# 6V_Boost_-_High_Current.net
KiCad netlist of a schematic drawn in Altium Designer
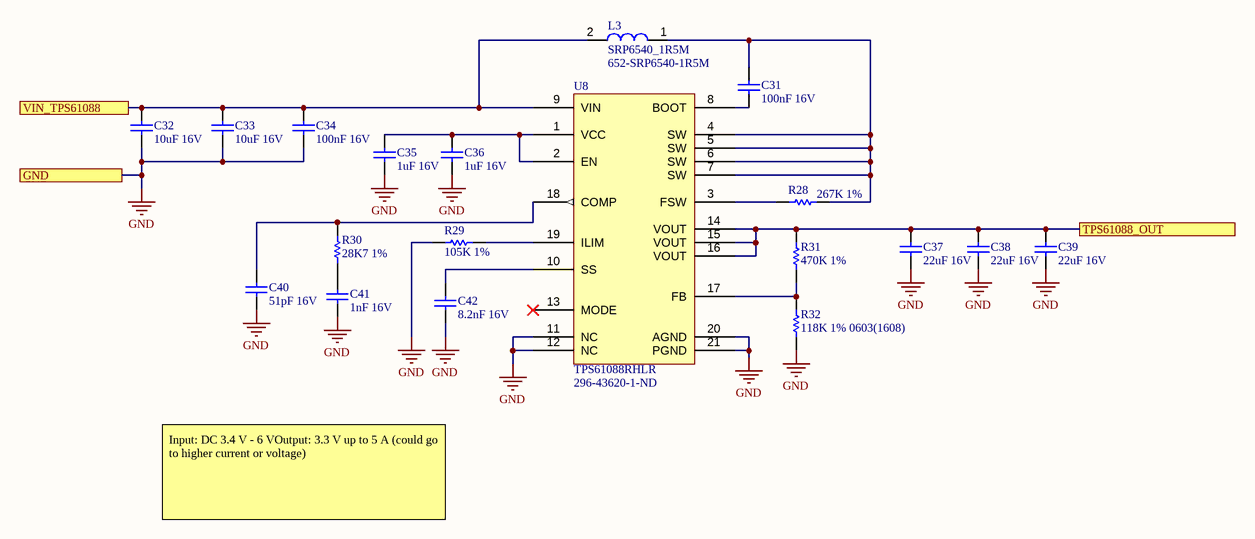
[diagram p0: 6V Boost - High Current.SchDoc]

(export (version "E")
  (design (tool "Eeschema 10.0.6"))
  (components
    (comp (ref "C31")
      (value "100nF 16V")
      (footprint "CAPC0603(1608)100_N")
      (description "CAP 100nF 16V ±10% 0603 (1608 Metric) Thickness 1mm SMD")
      (fields (field (name "TOLERANCE") "Â±10%"))
      (libsource (lib "Altium Content Vault") (part "CAP"))
    )
    (comp (ref "C32")
      (value "10uF 16V")
      (footprint "CAPC0805(2012)145_N")
      (description "CAP 10uF 16V ±10% 0805 (2012 Metric) Thickness 1.45mm SMD")
      (fields (field (name "TOLERANCE") "Â±10%"))
      (libsource (lib "Altium Content Vault") (part "CAP"))
    )
    (comp (ref "C33")
      (value "10uF 16V")
      (footprint "CAPC0805(2012)145_N")
      (description "CAP 10uF 16V ±10% 0805 (2012 Metric) Thickness 1.45mm SMD")
      (fields (field (name "TOLERANCE") "Â±10%"))
      (libsource (lib "Altium Content Vault") (part "CAP"))
    )
    (comp (ref "C34")
      (value "100nF 16V")
      (footprint "CAPC0603(1608)100_N")
      (description "CAP 100nF 16V ±10% 0603 (1608 Metric) Thickness 1mm SMD")
      (fields (field (name "TOLERANCE") "Â±10%"))
      (libsource (lib "Altium Content Vault") (part "CAP"))
    )
    (comp (ref "C35")
      (value "1uF 16V")
      (footprint "CAPC0603(1608)100_N")
      (description "CAP 1uF 16V ±5% 0603 (1608 Metric) Thickness 1mm SMD")
      (fields (field (name "TOLERANCE") "Â±5%"))
      (libsource (lib "Altium Content Vault") (part "CAP"))
    )
    (comp (ref "C36")
      (value "1uF 16V")
      (footprint "CAPC0603(1608)100_N")
      (description "CAP 1uF 16V ±5% 0603 (1608 Metric) Thickness 1mm SMD")
      (fields (field (name "TOLERANCE") "Â±5%"))
      (libsource (lib "Altium Content Vault") (part "CAP"))
    )
    (comp (ref "C37")
      (value "22uF 16V")
      (footprint "CAPC2220(5750)300_N")
      (description "CAP 22uF 16V ±20% 2220 (5750 Metric) Thickness 3mm SMD")
      (fields (field (name "TOLERANCE") "Â±20%"))
      (libsource (lib "Altium Content Vault") (part "CAP"))
    )
    (comp (ref "C38")
      (value "22uF 16V")
      (footprint "CAPC2220(5750)300_N")
      (description "CAP 22uF 16V ±20% 2220 (5750 Metric) Thickness 3mm SMD")
      (fields (field (name "TOLERANCE") "Â±20%"))
      (libsource (lib "Altium Content Vault") (part "CAP"))
    )
    (comp (ref "C39")
      (value "22uF 16V")
      (footprint "CAPC2220(5750)300_N")
      (description "CAP 22uF 16V ±20% 2220 (5750 Metric) Thickness 3mm SMD")
      (fields (field (name "TOLERANCE") "Â±20%"))
      (libsource (lib "Altium Content Vault") (part "CAP"))
    )
    (comp (ref "C40")
      (value "51pF 16V")
      (footprint "CAPC0603(1608)100_L")
      (description "CAP 51pF 16V ±5% 0603 (1608 Metric) Thickness 1mm SMD")
      (fields (field (name "TOLERANCE") "Â±5%"))
      (libsource (lib "Altium Content Vault") (part "CAP"))
    )
    (comp (ref "C41")
      (value "1nF 16V")
      (footprint "CAPC0603(1608)100_L")
      (description "CAP 1nF 16V ±1% 0603 (1608 Metric) Thickness 1mm SMD")
      (fields (field (name "TOLERANCE") "Â±1%"))
      (libsource (lib "Altium Content Vault") (part "CAP"))
    )
    (comp (ref "C42")
      (value "8.2nF 16V")
      (footprint "CAPC0603(1608)100_M")
      (description "CAP 8.2nF 16V ±5% 0603 (1608 Metric) Thickness 1mm SMD")
      (fields (field (name "TOLERANCE") "Â±5%"))
      (libsource (lib "Altium Content Vault") (part "CAP"))
    )
    (comp (ref "L3")
      (value "SRP6540_1R5M")
      (footprint "SRP6540_1R5M")
      (description "1.5µH Shielded Wirewound Inductor 11A 10 mOhm Max Nonstandard")
      (fields
        (field (name "MANUFACTURER") "Bourns")
        (field (name "MANUFACTURER PART NUMBER") "SRP6540-1R5M")
        (field (name "SUPPLIER PART NUMBER 1") "652-SRP6540-1R5M")
      )
      (libsource (lib "Components - 12.02.20 - 19.52") (part "CMP-00369-1"))
    )
    (comp (ref "R28")
      (value "267K 1%")
      (footprint "RESC0603(1608)_L")
      (description "267K 0.1W 1% 0603 (1608 Metric)  SMD")
      (fields (field (name "TOLERANCE") "1 %") (field (name "POWER") "0.1 W"))
      (libsource (lib "Altium Content Vault") (part "RES"))
    )
    (comp (ref "R29")
      (value "105K 1%")
      (footprint "RESC0603(1608)_L")
      (description "105K 0.1W 1% 0603 (1608 Metric)  SMD")
      (fields (field (name "TOLERANCE") "1 %") (field (name "POWER") "0.1 W"))
      (libsource (lib "Altium Content Vault") (part "RES"))
    )
    (comp (ref "R30")
      (value "28K7 1%")
      (footprint "RESC0603(1608)_L")
      (description "28K7 0.1W 1% 0603 (1608 Metric)  SMD")
      (fields (field (name "TOLERANCE") "1 %") (field (name "POWER") "0.1 W"))
      (libsource (lib "Altium Content Vault") (part "RES"))
    )
    (comp (ref "R31")
      (value "470K 1%")
      (footprint "RESC0603(1608)_L")
      (description "470K 0.1W 1% 0603 (1608 Metric)  SMD")
      (fields (field (name "POWER") "0.1 W") (field (name "TOLERANCE") "1 %"))
      (libsource (lib "Altium Content Vault") (part "RES"))
    )
    (comp (ref "R32")
      (value "118K 1% 0603(1608)")
      (footprint "RESC0603(1608)_M")
      (description "118K 0.1W 1% 0603 (1608 Metric)  SMD")
      (fields (field (name "POWER") "0.1 W") (field (name "TOLERANCE") "1 %"))
      (libsource (lib "Altium Content Vault") (part "RES"))
    )
    (comp (ref "U8")
      (value "TPS61088RHLR")
      (footprint "QFN50P450X350X100_HS-21N")
      (fields
        (field (name "MANUFACTURER") "Texas Instruments")
        (field (name "SUPPLIER PART NUMBER 1") "296-43620-1-ND")
      )
      (libsource (lib "Components - 12.02.20 - 19.48") (part "CMP-00368-3"))
    )
  )
  (nets
    (net (code "1") (name "/TPS61088_OUT") (class "Default")
      (node (ref "C37") (pin "1") (pinfunction "1_1") (pintype "passive"))
      (node (ref "C38") (pin "1") (pinfunction "1_1") (pintype "passive"))
      (node (ref "C39") (pin "1") (pinfunction "1_1") (pintype "passive"))
      (node (ref "R31") (pin "2") (pinfunction "2_2") (pintype "passive"))
      (node (ref "U8") (pin "14") (pinfunction "VOUT_14") (pintype "passive"))
      (node (ref "U8") (pin "15") (pinfunction "VOUT_15") (pintype "passive"))
      (node (ref "U8") (pin "16") (pinfunction "VOUT_16") (pintype "passive"))
    )
    (net (code "2") (name "/VIN_TPS61088") (class "Default")
      (node (ref "C32") (pin "2") (pinfunction "2_2") (pintype "passive"))
      (node (ref "C33") (pin "2") (pinfunction "2_2") (pintype "passive"))
      (node (ref "C34") (pin "2") (pinfunction "2_2") (pintype "passive"))
      (node (ref "L3") (pin "2") (pinfunction "2_2") (pintype "passive"))
      (node (ref "U8") (pin "9") (pinfunction "VIN_9") (pintype "passive"))
    )
    (net (code "3") (name "GND") (class "Default")
      (node (ref "C32") (pin "1") (pinfunction "1_1") (pintype "passive"))
      (node (ref "C33") (pin "1") (pinfunction "1_1") (pintype "passive"))
      (node (ref "C34") (pin "1") (pinfunction "1_1") (pintype "passive"))
      (node (ref "C35") (pin "1") (pinfunction "1_1") (pintype "passive"))
      (node (ref "C36") (pin "1") (pinfunction "1_1") (pintype "passive"))
      (node (ref "C37") (pin "2") (pinfunction "2_2") (pintype "passive"))
      (node (ref "C38") (pin "2") (pinfunction "2_2") (pintype "passive"))
      (node (ref "C39") (pin "2") (pinfunction "2_2") (pintype "passive"))
      (node (ref "C40") (pin "1") (pinfunction "1_1") (pintype "passive"))
      (node (ref "C41") (pin "1") (pinfunction "1_1") (pintype "passive"))
      (node (ref "C42") (pin "1") (pinfunction "1_1") (pintype "passive"))
      (node (ref "R29") (pin "1") (pinfunction "1_1") (pintype "passive"))
      (node (ref "R32") (pin "1") (pinfunction "1_1") (pintype "passive"))
      (node (ref "U8") (pin "11") (pinfunction "NC_11") (pintype "passive"))
      (node (ref "U8") (pin "12") (pinfunction "NC_12") (pintype "passive"))
      (node (ref "U8") (pin "20") (pinfunction "AGND_20") (pintype "passive"))
      (node (ref "U8") (pin "21") (pinfunction "PGND_21") (pintype "passive"))
    )
    (net (code "4") (name "Net-(C31-Pad2)") (class "Default")
      (node (ref "C31") (pin "2") (pinfunction "2_2") (pintype "passive"))
      (node (ref "L3") (pin "1") (pinfunction "1_1") (pintype "passive"))
      (node (ref "R28") (pin "1") (pinfunction "1_1") (pintype "passive"))
      (node (ref "U8") (pin "4") (pinfunction "SW_4") (pintype "passive"))
      (node (ref "U8") (pin "5") (pinfunction "SW_5") (pintype "passive"))
      (node (ref "U8") (pin "6") (pinfunction "SW_6") (pintype "passive"))
      (node (ref "U8") (pin "7") (pinfunction "SW_7") (pintype "passive"))
    )
    (net (code "5") (name "Net-(C41-Pad2)") (class "Default")
      (node (ref "C41") (pin "2") (pinfunction "2_2") (pintype "passive"))
      (node (ref "R30") (pin "1") (pinfunction "1_1") (pintype "passive"))
    )
    (net (code "6") (name "Net-(U8-BOOT)") (class "Default")
      (node (ref "C31") (pin "1") (pinfunction "1_1") (pintype "passive"))
      (node (ref "U8") (pin "8") (pinfunction "BOOT_8") (pintype "passive"))
    )
    (net (code "7") (name "Net-(U8-COMP)") (class "Default")
      (node (ref "C40") (pin "2") (pinfunction "2_2") (pintype "passive"))
      (node (ref "R30") (pin "2") (pinfunction "2_2") (pintype "passive"))
      (node (ref "U8") (pin "18") (pinfunction "COMP_18") (pintype "output"))
    )
    (net (code "8") (name "Net-(U8-EN)") (class "Default")
      (node (ref "C35") (pin "2") (pinfunction "2_2") (pintype "passive"))
      (node (ref "C36") (pin "2") (pinfunction "2_2") (pintype "passive"))
      (node (ref "U8") (pin "1") (pinfunction "VCC_1") (pintype "passive"))
      (node (ref "U8") (pin "2") (pinfunction "EN_2") (pintype "passive"))
    )
    (net (code "9") (name "Net-(U8-FB)") (class "Default")
      (node (ref "R31") (pin "1") (pinfunction "1_1") (pintype "passive"))
      (node (ref "R32") (pin "2") (pinfunction "2_2") (pintype "passive"))
      (node (ref "U8") (pin "17") (pinfunction "FB_17") (pintype "passive"))
    )
    (net (code "10") (name "Net-(U8-FSW)") (class "Default")
      (node (ref "R28") (pin "2") (pinfunction "2_2") (pintype "passive"))
      (node (ref "U8") (pin "3") (pinfunction "FSW_3") (pintype "passive"))
    )
    (net (code "11") (name "Net-(U8-ILIM)") (class "Default")
      (node (ref "R29") (pin "2") (pinfunction "2_2") (pintype "passive"))
      (node (ref "U8") (pin "19") (pinfunction "ILIM_19") (pintype "passive"))
    )
    (net (code "12") (name "Net-(U8-SS)") (class "Default")
      (node (ref "C42") (pin "2") (pinfunction "2_2") (pintype "passive"))
      (node (ref "U8") (pin "10") (pinfunction "SS_10") (pintype "passive"))
    )
    (net (code "13") (name "unconnected-(U8-MODE-Pad13)") (class "Default")
      (node (ref "U8") (pin "13") (pinfunction "MODE_13") (pintype "passive+no_connect"))
    )
  )
)
